# calibratorSimple.net
KiCad netlist of a schematic drawn in EAGLE
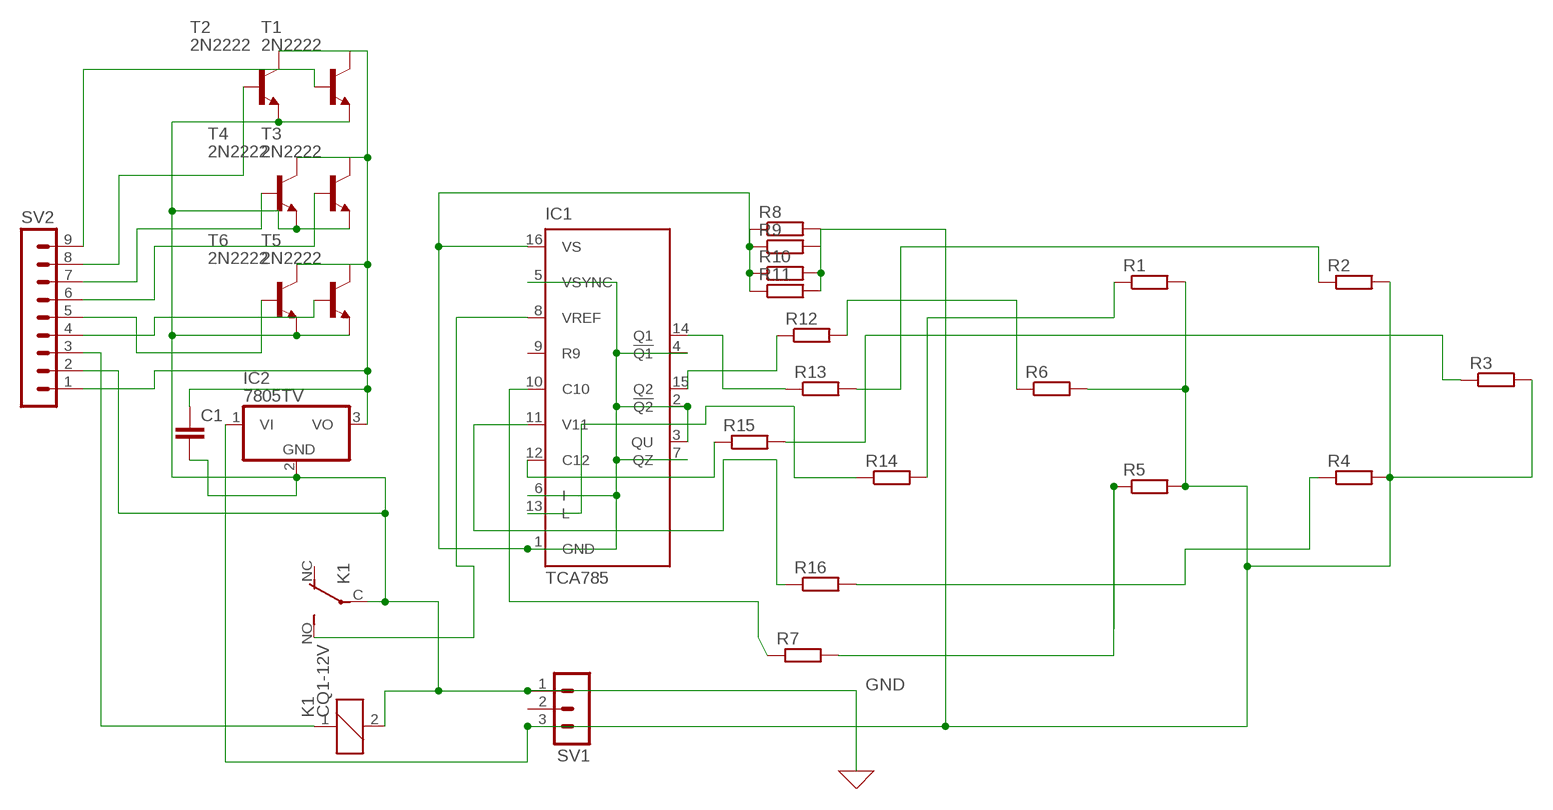
[diagram p0: schematic, sheet 1]

(export (version "E")
  (design (tool "Eeschema 10.0.6"))
  (components
    (comp (ref "C1")
      (value "C2.5/2")
      (footprint "eagle-import:C2.5-2")
      (libsource (lib "eagle-import") (part "C2.5/2"))
    )
    (comp (ref "IC1")
      (value "TCA785")
      (footprint "eagle-import:DIL16")
      (libsource (lib "eagle-import") (part "TCA785"))
    )
    (comp (ref "IC2")
      (value "7805TV")
      (footprint "eagle-import:TO220V")
      (libsource (lib "eagle-import") (part "78TV05"))
    )
    (comp (ref "K1")
      (value "CQ1-12V")
      (footprint "eagle-import:CQ1")
      (libsource (lib "eagle-import") (part "CQ1-12V"))
    )
    (comp (ref "R1")
      (value "R-EU_0207/15")
      (footprint "eagle-import:0207_15")
      (libsource (lib "eagle-import") (part "R-EU_0207/15"))
    )
    (comp (ref "R2")
      (value "R-EU_0207/15")
      (footprint "eagle-import:0207_15")
      (libsource (lib "eagle-import") (part "R-EU_0207/15"))
    )
    (comp (ref "R3")
      (value "R-EU_0207/15")
      (footprint "eagle-import:0207_15")
      (libsource (lib "eagle-import") (part "R-EU_0207/15"))
    )
    (comp (ref "R4")
      (value "R-EU_0207/15")
      (footprint "eagle-import:0207_15")
      (libsource (lib "eagle-import") (part "R-EU_0207/15"))
    )
    (comp (ref "R5")
      (value "R-EU_0207/15")
      (footprint "eagle-import:0207_15")
      (libsource (lib "eagle-import") (part "R-EU_0207/15"))
    )
    (comp (ref "R6")
      (value "R-EU_0207/15")
      (footprint "eagle-import:0207_15")
      (libsource (lib "eagle-import") (part "R-EU_0207/15"))
    )
    (comp (ref "R7")
      (value "R-EU_0204/7")
      (footprint "eagle-import:0204_7")
      (libsource (lib "eagle-import") (part "R-EU_0204/7"))
    )
    (comp (ref "R8")
      (value "R-EU_0204/7")
      (footprint "eagle-import:0204_7")
      (libsource (lib "eagle-import") (part "R-EU_0204/7"))
    )
    (comp (ref "R9")
      (value "R-EU_0204/7")
      (footprint "eagle-import:0204_7")
      (libsource (lib "eagle-import") (part "R-EU_0204/7"))
    )
    (comp (ref "R10")
      (value "R-EU_0204/7")
      (footprint "eagle-import:0204_7")
      (libsource (lib "eagle-import") (part "R-EU_0204/7"))
    )
    (comp (ref "R11")
      (value "R-EU_0204/7")
      (footprint "eagle-import:0204_7")
      (libsource (lib "eagle-import") (part "R-EU_0204/7"))
    )
    (comp (ref "R12")
      (value "R-EU_0204/7")
      (footprint "eagle-import:0204_7")
      (libsource (lib "eagle-import") (part "R-EU_0204/7"))
    )
    (comp (ref "R13")
      (value "R-EU_0204/7")
      (footprint "eagle-import:0204_7")
      (libsource (lib "eagle-import") (part "R-EU_0204/7"))
    )
    (comp (ref "R14")
      (value "R-EU_0204/7")
      (footprint "eagle-import:0204_7")
      (libsource (lib "eagle-import") (part "R-EU_0204/7"))
    )
    (comp (ref "R15")
      (value "R-EU_0204/7")
      (footprint "eagle-import:0204_7")
      (libsource (lib "eagle-import") (part "R-EU_0204/7"))
    )
    (comp (ref "R16")
      (value "R-EU_0204/7")
      (footprint "eagle-import:0204_7")
      (libsource (lib "eagle-import") (part "R-EU_0204/7"))
    )
    (comp (ref "SV1")
      (value "MA03-1")
      (footprint "eagle-import:MA03-1")
      (libsource (lib "eagle-import") (part "MA03-1"))
    )
    (comp (ref "SV2")
      (value "MA09-1")
      (footprint "eagle-import:MA09-1")
      (libsource (lib "eagle-import") (part "MA09-1"))
    )
    (comp (ref "T1")
      (value "2N2222")
      (footprint "eagle-import:TO18")
      (libsource (lib "eagle-import") (part "2N2222"))
    )
    (comp (ref "T2")
      (value "2N2222")
      (footprint "eagle-import:TO18")
      (libsource (lib "eagle-import") (part "2N2222"))
    )
    (comp (ref "T3")
      (value "2N2222")
      (footprint "eagle-import:TO18")
      (libsource (lib "eagle-import") (part "2N2222"))
    )
    (comp (ref "T4")
      (value "2N2222")
      (footprint "eagle-import:TO18")
      (libsource (lib "eagle-import") (part "2N2222"))
    )
    (comp (ref "T5")
      (value "2N2222")
      (footprint "eagle-import:TO18")
      (libsource (lib "eagle-import") (part "2N2222"))
    )
    (comp (ref "T6")
      (value "2N2222")
      (footprint "eagle-import:TO18")
      (libsource (lib "eagle-import") (part "2N2222"))
    )
  )
  (nets
    (net (code "1") (name "GND") (class "Default")
      (node (ref "C1") (pin "2") (pinfunction "2_2") (pintype "passive"))
      (node (ref "IC2") (pin "2") (pinfunction "GND_2") (pintype "passive"))
      (node (ref "K1") (pin "2") (pinfunction "2_2") (pintype "passive"))
      (node (ref "K1") (pin "C") (pinfunction "P_C") (pintype "passive"))
      (node (ref "SV1") (pin "1") (pinfunction "1_1") (pintype "passive"))
      (node (ref "SV2") (pin "2") (pinfunction "2_2") (pintype "passive"))
      (node (ref "T1") (pin "1") (pinfunction "E_1") (pintype "passive"))
      (node (ref "T2") (pin "1") (pinfunction "E_1") (pintype "passive"))
      (node (ref "T3") (pin "1") (pinfunction "E_1") (pintype "passive"))
      (node (ref "T4") (pin "1") (pinfunction "E_1") (pintype "passive"))
      (node (ref "T5") (pin "1") (pinfunction "E_1") (pintype "passive"))
      (node (ref "T6") (pin "1") (pinfunction "E_1") (pintype "passive"))
    )
    (net (code "2") (name "Net-(IC1-C10)") (class "Default")
      (node (ref "IC1") (pin "10") (pinfunction "C10_10") (pintype "input"))
      (node (ref "R7") (pin "1") (pinfunction "1_1") (pintype "passive"))
    )
    (net (code "3") (name "Net-(IC1-C12)") (class "Default")
      (node (ref "IC1") (pin "12") (pinfunction "C12_12") (pintype "input"))
      (node (ref "R15") (pin "1") (pinfunction "1_1") (pintype "passive"))
    )
    (net (code "4") (name "Net-(IC1-GND)") (class "Default")
      (node (ref "IC1") (pin "1") (pinfunction "GND_1") (pintype "power_in"))
      (node (ref "IC1") (pin "16") (pinfunction "VS_16") (pintype "input"))
      (node (ref "IC1") (pin "2") (pinfunction "~{Q2}_2") (pintype "output"))
      (node (ref "IC1") (pin "3") (pinfunction "QU_3") (pintype "output"))
      (node (ref "IC1") (pin "4") (pinfunction "~{Q1}_4") (pintype "output"))
      (node (ref "IC1") (pin "5") (pinfunction "VSYNC_5") (pintype "input"))
      (node (ref "IC1") (pin "6") (pinfunction "I_6") (pintype "input"))
      (node (ref "IC1") (pin "7") (pinfunction "QZ_7") (pintype "output"))
      (node (ref "R10") (pin "1") (pinfunction "1_1") (pintype "passive"))
      (node (ref "R11") (pin "1") (pinfunction "1_1") (pintype "passive"))
      (node (ref "R8") (pin "1") (pinfunction "1_1") (pintype "passive"))
      (node (ref "R9") (pin "1") (pinfunction "1_1") (pintype "passive"))
    )
    (net (code "5") (name "Net-(IC1-L)") (class "Default")
      (node (ref "IC1") (pin "13") (pinfunction "L_13") (pintype "input"))
      (node (ref "R14") (pin "1") (pinfunction "1_1") (pintype "passive"))
    )
    (net (code "6") (name "Net-(IC1-Q1)") (class "Default")
      (node (ref "IC1") (pin "14") (pinfunction "Q1_14") (pintype "output"))
      (node (ref "R13") (pin "1") (pinfunction "1_1") (pintype "passive"))
    )
    (net (code "7") (name "Net-(IC1-Q2)") (class "Default")
      (node (ref "IC1") (pin "15") (pinfunction "Q2_15") (pintype "output"))
      (node (ref "R12") (pin "1") (pinfunction "1_1") (pintype "passive"))
    )
    (net (code "8") (name "Net-(IC1-V11)") (class "Default")
      (node (ref "IC1") (pin "11") (pinfunction "V11_11") (pintype "input"))
      (node (ref "R16") (pin "1") (pinfunction "1_1") (pintype "passive"))
    )
    (net (code "9") (name "Net-(IC1-VREF)") (class "Default")
      (node (ref "IC1") (pin "8") (pinfunction "VREF_8") (pintype "input"))
      (node (ref "K1") (pin "NO") (pinfunction "S_NO") (pintype "passive"))
    )
    (net (code "10") (name "Net-(IC2-VI)") (class "Default")
      (node (ref "IC2") (pin "1") (pinfunction "VI_1") (pintype "input"))
      (node (ref "R1") (pin "2") (pinfunction "2_2") (pintype "passive"))
      (node (ref "R10") (pin "2") (pinfunction "2_2") (pintype "passive"))
      (node (ref "R11") (pin "2") (pinfunction "2_2") (pintype "passive"))
      (node (ref "R2") (pin "2") (pinfunction "2_2") (pintype "passive"))
      (node (ref "R3") (pin "2") (pinfunction "2_2") (pintype "passive"))
      (node (ref "R4") (pin "2") (pinfunction "2_2") (pintype "passive"))
      (node (ref "R5") (pin "2") (pinfunction "2_2") (pintype "passive"))
      (node (ref "R6") (pin "2") (pinfunction "2_2") (pintype "passive"))
      (node (ref "R8") (pin "2") (pinfunction "2_2") (pintype "passive"))
      (node (ref "R9") (pin "2") (pinfunction "2_2") (pintype "passive"))
      (node (ref "SV1") (pin "3") (pinfunction "3_3") (pintype "passive"))
    )
    (net (code "11") (name "Net-(IC2-VO)") (class "Default")
      (node (ref "C1") (pin "1") (pinfunction "1_1") (pintype "passive"))
      (node (ref "IC2") (pin "3") (pinfunction "VO_3") (pintype "passive"))
      (node (ref "SV2") (pin "1") (pinfunction "1_1") (pintype "passive"))
      (node (ref "T1") (pin "3") (pinfunction "C_3") (pintype "passive"))
      (node (ref "T2") (pin "3") (pinfunction "C_3") (pintype "passive"))
      (node (ref "T3") (pin "3") (pinfunction "C_3") (pintype "passive"))
      (node (ref "T4") (pin "3") (pinfunction "C_3") (pintype "passive"))
      (node (ref "T5") (pin "3") (pinfunction "C_3") (pintype "passive"))
      (node (ref "T6") (pin "3") (pinfunction "C_3") (pintype "passive"))
    )
    (net (code "12") (name "Net-(K1-Pad1)") (class "Default")
      (node (ref "K1") (pin "1") (pinfunction "1_1") (pintype "passive"))
      (node (ref "SV2") (pin "3") (pinfunction "3_3") (pintype "passive"))
    )
    (net (code "13") (name "Net-(R1-Pad1)") (class "Default")
      (node (ref "R1") (pin "1") (pinfunction "1_1") (pintype "passive"))
      (node (ref "R14") (pin "2") (pinfunction "2_2") (pintype "passive"))
    )
    (net (code "14") (name "Net-(R5-Pad1)") (class "Default")
      (node (ref "R5") (pin "1") (pinfunction "1_1") (pintype "passive"))
      (node (ref "R7") (pin "2") (pinfunction "2_2") (pintype "passive"))
    )
    (net (code "15") (name "Net-(R12-Pad2)") (class "Default")
      (node (ref "R12") (pin "2") (pinfunction "2_2") (pintype "passive"))
      (node (ref "R6") (pin "1") (pinfunction "1_1") (pintype "passive"))
    )
    (net (code "16") (name "Net-(R13-Pad2)") (class "Default")
      (node (ref "R13") (pin "2") (pinfunction "2_2") (pintype "passive"))
      (node (ref "R2") (pin "1") (pinfunction "1_1") (pintype "passive"))
    )
    (net (code "17") (name "Net-(R15-Pad2)") (class "Default")
      (node (ref "R15") (pin "2") (pinfunction "2_2") (pintype "passive"))
      (node (ref "R3") (pin "1") (pinfunction "1_1") (pintype "passive"))
    )
    (net (code "18") (name "Net-(R16-Pad2)") (class "Default")
      (node (ref "R16") (pin "2") (pinfunction "2_2") (pintype "passive"))
      (node (ref "R4") (pin "1") (pinfunction "1_1") (pintype "passive"))
    )
    (net (code "19") (name "Net-(T1-B)") (class "Default")
      (node (ref "SV2") (pin "9") (pinfunction "9_9") (pintype "passive"))
      (node (ref "T1") (pin "2") (pinfunction "B_2") (pintype "passive"))
    )
    (net (code "20") (name "Net-(T2-B)") (class "Default")
      (node (ref "SV2") (pin "8") (pinfunction "8_8") (pintype "passive"))
      (node (ref "T2") (pin "2") (pinfunction "B_2") (pintype "passive"))
    )
    (net (code "21") (name "Net-(T3-B)") (class "Default")
      (node (ref "SV2") (pin "6") (pinfunction "6_6") (pintype "passive"))
      (node (ref "T3") (pin "2") (pinfunction "B_2") (pintype "passive"))
    )
    (net (code "22") (name "Net-(T4-B)") (class "Default")
      (node (ref "SV2") (pin "7") (pinfunction "7_7") (pintype "passive"))
      (node (ref "T4") (pin "2") (pinfunction "B_2") (pintype "passive"))
    )
    (net (code "23") (name "Net-(T5-B)") (class "Default")
      (node (ref "SV2") (pin "4") (pinfunction "4_4") (pintype "passive"))
      (node (ref "T5") (pin "2") (pinfunction "B_2") (pintype "passive"))
    )
    (net (code "24") (name "Net-(T6-B)") (class "Default")
      (node (ref "SV2") (pin "5") (pinfunction "5_5") (pintype "passive"))
      (node (ref "T6") (pin "2") (pinfunction "B_2") (pintype "passive"))
    )
    (net (code "25") (name "unconnected-(IC1-R9-Pad9)") (class "Default")
      (node (ref "IC1") (pin "9") (pinfunction "R9_9") (pintype "input"))
    )
    (net (code "26") (name "unconnected-(K1B-O-PadNC)") (class "Default")
      (node (ref "K1") (pin "NC") (pinfunction "O_NC") (pintype "passive"))
    )
    (net (code "27") (name "unconnected-(SV1-Pad2)") (class "Default")
      (node (ref "SV1") (pin "2") (pinfunction "2_2") (pintype "passive"))
    )
  )
)
